# 5853-base-board.net
KiCad netlist of a schematic drawn in EAGLE
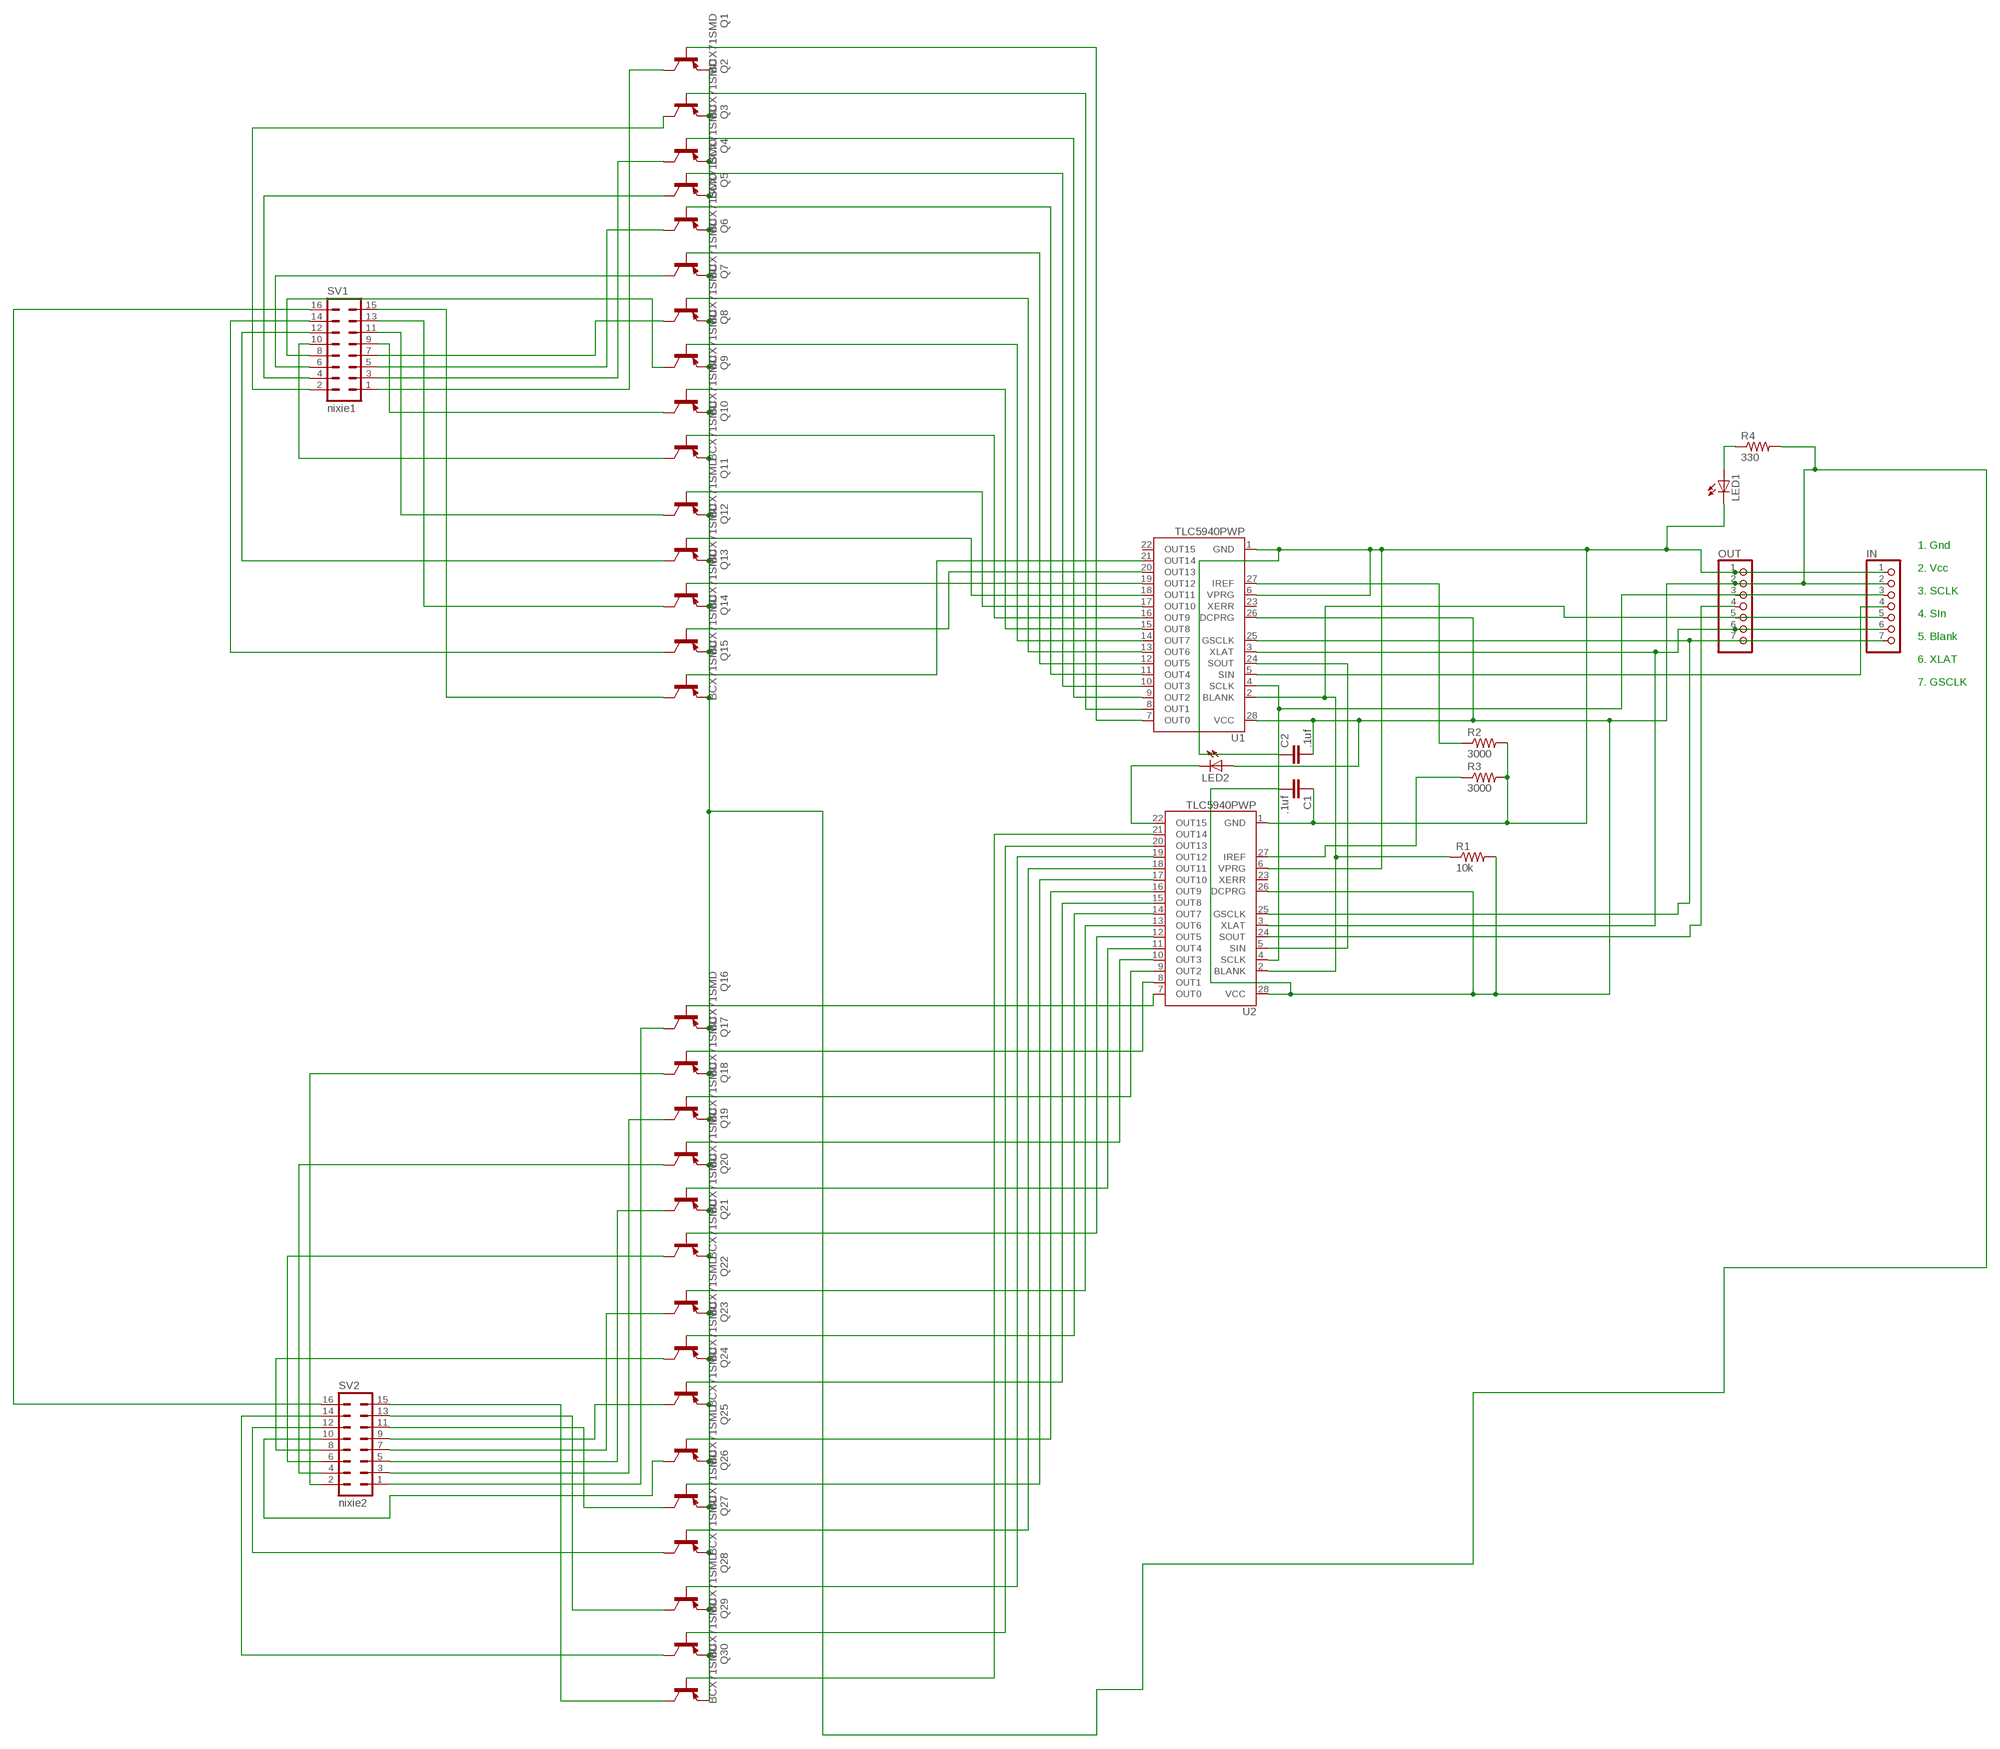
[diagram p0: schematic, sheet 1]

(export (version "E")
  (design (tool "Eeschema 10.0.6"))
  (components
    (comp (ref "C1")
      (value ".1uf")
      (footprint "eagle-import:C0805K")
      (libsource (lib "eagle-import") (part "C-EUC0805K"))
    )
    (comp (ref "C2")
      (value ".1uf")
      (footprint "eagle-import:C0805K")
      (libsource (lib "eagle-import") (part "C-EUC0805K"))
    )
    (comp (ref "IN")
      (value "PINHD-1X7")
      (footprint "eagle-import:1X07")
      (libsource (lib "eagle-import") (part "PINHD-1X7"))
    )
    (comp (ref "LED1")
      (value "LEDCHIPLED_0603")
      (footprint "eagle-import:CHIPLED_0603")
      (libsource (lib "eagle-import") (part "LEDCHIPLED_0603"))
    )
    (comp (ref "LED2")
      (value "LEDCHIPLED_0603")
      (footprint "eagle-import:CHIPLED_0603")
      (libsource (lib "eagle-import") (part "LEDCHIPLED_0603"))
    )
    (comp (ref "OUT")
      (value "PINHD-1X7")
      (footprint "eagle-import:1X07")
      (libsource (lib "eagle-import") (part "PINHD-1X7"))
    )
    (comp (ref "Q1")
      (value "BCX71SMD")
      (footprint "eagle-import:SOT23")
      (libsource (lib "eagle-import") (part "BCX71SMD"))
    )
    (comp (ref "Q2")
      (value "BCX71SMD")
      (footprint "eagle-import:SOT23")
      (libsource (lib "eagle-import") (part "BCX71SMD"))
    )
    (comp (ref "Q3")
      (value "BCX71SMD")
      (footprint "eagle-import:SOT23")
      (libsource (lib "eagle-import") (part "BCX71SMD"))
    )
    (comp (ref "Q4")
      (value "BCX71SMD")
      (footprint "eagle-import:SOT23")
      (libsource (lib "eagle-import") (part "BCX71SMD"))
    )
    (comp (ref "Q5")
      (value "BCX71SMD")
      (footprint "eagle-import:SOT23")
      (libsource (lib "eagle-import") (part "BCX71SMD"))
    )
    (comp (ref "Q6")
      (value "BCX71SMD")
      (footprint "eagle-import:SOT23")
      (libsource (lib "eagle-import") (part "BCX71SMD"))
    )
    (comp (ref "Q7")
      (value "BCX71SMD")
      (footprint "eagle-import:SOT23")
      (libsource (lib "eagle-import") (part "BCX71SMD"))
    )
    (comp (ref "Q8")
      (value "BCX71SMD")
      (footprint "eagle-import:SOT23")
      (libsource (lib "eagle-import") (part "BCX71SMD"))
    )
    (comp (ref "Q9")
      (value "BCX71SMD")
      (footprint "eagle-import:SOT23")
      (libsource (lib "eagle-import") (part "BCX71SMD"))
    )
    (comp (ref "Q10")
      (value "BCX71SMD")
      (footprint "eagle-import:SOT23")
      (libsource (lib "eagle-import") (part "BCX71SMD"))
    )
    (comp (ref "Q11")
      (value "BCX71SMD")
      (footprint "eagle-import:SOT23")
      (libsource (lib "eagle-import") (part "BCX71SMD"))
    )
    (comp (ref "Q12")
      (value "BCX71SMD")
      (footprint "eagle-import:SOT23")
      (libsource (lib "eagle-import") (part "BCX71SMD"))
    )
    (comp (ref "Q13")
      (value "BCX71SMD")
      (footprint "eagle-import:SOT23")
      (libsource (lib "eagle-import") (part "BCX71SMD"))
    )
    (comp (ref "Q14")
      (value "BCX71SMD")
      (footprint "eagle-import:SOT23")
      (libsource (lib "eagle-import") (part "BCX71SMD"))
    )
    (comp (ref "Q15")
      (value "BCX71SMD")
      (footprint "eagle-import:SOT23")
      (libsource (lib "eagle-import") (part "BCX71SMD"))
    )
    (comp (ref "Q16")
      (value "BCX71SMD")
      (footprint "eagle-import:SOT23")
      (libsource (lib "eagle-import") (part "BCX71SMD"))
    )
    (comp (ref "Q17")
      (value "BCX71SMD")
      (footprint "eagle-import:SOT23")
      (libsource (lib "eagle-import") (part "BCX71SMD"))
    )
    (comp (ref "Q18")
      (value "BCX71SMD")
      (footprint "eagle-import:SOT23")
      (libsource (lib "eagle-import") (part "BCX71SMD"))
    )
    (comp (ref "Q19")
      (value "BCX71SMD")
      (footprint "eagle-import:SOT23")
      (libsource (lib "eagle-import") (part "BCX71SMD"))
    )
    (comp (ref "Q20")
      (value "BCX71SMD")
      (footprint "eagle-import:SOT23")
      (libsource (lib "eagle-import") (part "BCX71SMD"))
    )
    (comp (ref "Q21")
      (value "BCX71SMD")
      (footprint "eagle-import:SOT23")
      (libsource (lib "eagle-import") (part "BCX71SMD"))
    )
    (comp (ref "Q22")
      (value "BCX71SMD")
      (footprint "eagle-import:SOT23")
      (libsource (lib "eagle-import") (part "BCX71SMD"))
    )
    (comp (ref "Q23")
      (value "BCX71SMD")
      (footprint "eagle-import:SOT23")
      (libsource (lib "eagle-import") (part "BCX71SMD"))
    )
    (comp (ref "Q24")
      (value "BCX71SMD")
      (footprint "eagle-import:SOT23")
      (libsource (lib "eagle-import") (part "BCX71SMD"))
    )
    (comp (ref "Q25")
      (value "BCX71SMD")
      (footprint "eagle-import:SOT23")
      (libsource (lib "eagle-import") (part "BCX71SMD"))
    )
    (comp (ref "Q26")
      (value "BCX71SMD")
      (footprint "eagle-import:SOT23")
      (libsource (lib "eagle-import") (part "BCX71SMD"))
    )
    (comp (ref "Q27")
      (value "BCX71SMD")
      (footprint "eagle-import:SOT23")
      (libsource (lib "eagle-import") (part "BCX71SMD"))
    )
    (comp (ref "Q28")
      (value "BCX71SMD")
      (footprint "eagle-import:SOT23")
      (libsource (lib "eagle-import") (part "BCX71SMD"))
    )
    (comp (ref "Q29")
      (value "BCX71SMD")
      (footprint "eagle-import:SOT23")
      (libsource (lib "eagle-import") (part "BCX71SMD"))
    )
    (comp (ref "Q30")
      (value "BCX71SMD")
      (footprint "eagle-import:SOT23")
      (libsource (lib "eagle-import") (part "BCX71SMD"))
    )
    (comp (ref "R1")
      (value "10k")
      (footprint "eagle-import:R0603")
      (libsource (lib "eagle-import") (part "R-US_R0603"))
    )
    (comp (ref "R2")
      (value "3000")
      (footprint "eagle-import:R0603")
      (libsource (lib "eagle-import") (part "R-US_R0603"))
    )
    (comp (ref "R3")
      (value "3000")
      (footprint "eagle-import:R0603")
      (libsource (lib "eagle-import") (part "R-US_R0603"))
    )
    (comp (ref "R4")
      (value "330")
      (footprint "eagle-import:R0603")
      (libsource (lib "eagle-import") (part "R-US_R0603"))
    )
    (comp (ref "SV1")
      (value "nixie1")
      (footprint "eagle-import:ML16")
      (libsource (lib "eagle-import") (part "ML16"))
    )
    (comp (ref "SV2")
      (value "nixie2")
      (footprint "eagle-import:ML16")
      (libsource (lib "eagle-import") (part "ML16"))
    )
    (comp (ref "U1")
      (value "TLC5940PWP")
      (footprint "eagle-import:TSSOP28-GROUNDPAD")
      (libsource (lib "eagle-import") (part "TLC5940PWP"))
    )
    (comp (ref "U2")
      (value "TLC5940PWP")
      (footprint "eagle-import:TSSOP28-GROUNDPAD")
      (libsource (lib "eagle-import") (part "TLC5940PWP"))
    )
  )
  (nets
    (net (code "1") (name "Net-(LED1-PadA)") (class "Default")
      (node (ref "LED1") (pin "A") (pinfunction "A_A") (pintype "passive"))
      (node (ref "R4") (pin "1") (pinfunction "1_1") (pintype "passive"))
    )
    (net (code "2") (name "Net-(Q1-B)") (class "Default")
      (node (ref "Q1") (pin "1") (pinfunction "B_1") (pintype "passive"))
      (node (ref "U1") (pin "7") (pinfunction "OUT0_7") (pintype "bidirectional"))
    )
    (net (code "3") (name "Net-(Q1-C)") (class "Default")
      (node (ref "Q1") (pin "3") (pinfunction "C_3") (pintype "passive"))
      (node (ref "SV1") (pin "1") (pinfunction "1_1") (pintype "passive"))
    )
    (net (code "4") (name "Net-(Q1-E)") (class "Default")
      (node (ref "C1") (pin "2") (pinfunction "2_2") (pintype "passive"))
      (node (ref "C2") (pin "2") (pinfunction "2_2") (pintype "passive"))
      (node (ref "IN") (pin "2") (pinfunction "2_2") (pintype "passive"))
      (node (ref "LED2") (pin "A") (pinfunction "A_A") (pintype "passive"))
      (node (ref "OUT") (pin "2") (pinfunction "2_2") (pintype "passive"))
      (node (ref "Q1") (pin "2") (pinfunction "E_2") (pintype "passive"))
      (node (ref "Q10") (pin "2") (pinfunction "E_2") (pintype "passive"))
      (node (ref "Q11") (pin "2") (pinfunction "E_2") (pintype "passive"))
      (node (ref "Q12") (pin "2") (pinfunction "E_2") (pintype "passive"))
      (node (ref "Q13") (pin "2") (pinfunction "E_2") (pintype "passive"))
      (node (ref "Q14") (pin "2") (pinfunction "E_2") (pintype "passive"))
      (node (ref "Q15") (pin "2") (pinfunction "E_2") (pintype "passive"))
      (node (ref "Q16") (pin "2") (pinfunction "E_2") (pintype "passive"))
      (node (ref "Q17") (pin "2") (pinfunction "E_2") (pintype "passive"))
      (node (ref "Q18") (pin "2") (pinfunction "E_2") (pintype "passive"))
      (node (ref "Q19") (pin "2") (pinfunction "E_2") (pintype "passive"))
      (node (ref "Q2") (pin "2") (pinfunction "E_2") (pintype "passive"))
      (node (ref "Q20") (pin "2") (pinfunction "E_2") (pintype "passive"))
      (node (ref "Q21") (pin "2") (pinfunction "E_2") (pintype "passive"))
      (node (ref "Q22") (pin "2") (pinfunction "E_2") (pintype "passive"))
      (node (ref "Q23") (pin "2") (pinfunction "E_2") (pintype "passive"))
      (node (ref "Q24") (pin "2") (pinfunction "E_2") (pintype "passive"))
      (node (ref "Q25") (pin "2") (pinfunction "E_2") (pintype "passive"))
      (node (ref "Q26") (pin "2") (pinfunction "E_2") (pintype "passive"))
      (node (ref "Q27") (pin "2") (pinfunction "E_2") (pintype "passive"))
      (node (ref "Q28") (pin "2") (pinfunction "E_2") (pintype "passive"))
      (node (ref "Q29") (pin "2") (pinfunction "E_2") (pintype "passive"))
      (node (ref "Q3") (pin "2") (pinfunction "E_2") (pintype "passive"))
      (node (ref "Q30") (pin "2") (pinfunction "E_2") (pintype "passive"))
      (node (ref "Q4") (pin "2") (pinfunction "E_2") (pintype "passive"))
      (node (ref "Q5") (pin "2") (pinfunction "E_2") (pintype "passive"))
      (node (ref "Q6") (pin "2") (pinfunction "E_2") (pintype "passive"))
      (node (ref "Q7") (pin "2") (pinfunction "E_2") (pintype "passive"))
      (node (ref "Q8") (pin "2") (pinfunction "E_2") (pintype "passive"))
      (node (ref "Q9") (pin "2") (pinfunction "E_2") (pintype "passive"))
      (node (ref "R1") (pin "2") (pinfunction "2_2") (pintype "passive"))
      (node (ref "R4") (pin "2") (pinfunction "2_2") (pintype "passive"))
      (node (ref "U1") (pin "26") (pinfunction "DCPRG_26") (pintype "bidirectional"))
      (node (ref "U1") (pin "28") (pinfunction "VCC_28") (pintype "bidirectional"))
      (node (ref "U2") (pin "26") (pinfunction "DCPRG_26") (pintype "bidirectional"))
      (node (ref "U2") (pin "28") (pinfunction "VCC_28") (pintype "bidirectional"))
    )
    (net (code "5") (name "Net-(Q2-B)") (class "Default")
      (node (ref "Q2") (pin "1") (pinfunction "B_1") (pintype "passive"))
      (node (ref "U1") (pin "8") (pinfunction "OUT1_8") (pintype "bidirectional"))
    )
    (net (code "6") (name "Net-(Q2-C)") (class "Default")
      (node (ref "Q2") (pin "3") (pinfunction "C_3") (pintype "passive"))
      (node (ref "SV1") (pin "2") (pinfunction "2_2") (pintype "passive"))
    )
    (net (code "7") (name "Net-(Q3-B)") (class "Default")
      (node (ref "Q3") (pin "1") (pinfunction "B_1") (pintype "passive"))
      (node (ref "U1") (pin "9") (pinfunction "OUT2_9") (pintype "bidirectional"))
    )
    (net (code "8") (name "Net-(Q3-C)") (class "Default")
      (node (ref "Q3") (pin "3") (pinfunction "C_3") (pintype "passive"))
      (node (ref "SV1") (pin "3") (pinfunction "3_3") (pintype "passive"))
    )
    (net (code "9") (name "Net-(Q4-B)") (class "Default")
      (node (ref "Q4") (pin "1") (pinfunction "B_1") (pintype "passive"))
      (node (ref "U1") (pin "10") (pinfunction "OUT3_10") (pintype "bidirectional"))
    )
    (net (code "10") (name "Net-(Q4-C)") (class "Default")
      (node (ref "Q4") (pin "3") (pinfunction "C_3") (pintype "passive"))
      (node (ref "SV1") (pin "4") (pinfunction "4_4") (pintype "passive"))
    )
    (net (code "11") (name "Net-(Q5-B)") (class "Default")
      (node (ref "Q5") (pin "1") (pinfunction "B_1") (pintype "passive"))
      (node (ref "U1") (pin "11") (pinfunction "OUT4_11") (pintype "bidirectional"))
    )
    (net (code "12") (name "Net-(Q5-C)") (class "Default")
      (node (ref "Q5") (pin "3") (pinfunction "C_3") (pintype "passive"))
      (node (ref "SV1") (pin "5") (pinfunction "5_5") (pintype "passive"))
    )
    (net (code "13") (name "Net-(Q6-B)") (class "Default")
      (node (ref "Q6") (pin "1") (pinfunction "B_1") (pintype "passive"))
      (node (ref "U1") (pin "12") (pinfunction "OUT5_12") (pintype "bidirectional"))
    )
    (net (code "14") (name "Net-(Q6-C)") (class "Default")
      (node (ref "Q6") (pin "3") (pinfunction "C_3") (pintype "passive"))
      (node (ref "SV1") (pin "6") (pinfunction "6_6") (pintype "passive"))
    )
    (net (code "15") (name "Net-(Q7-B)") (class "Default")
      (node (ref "Q7") (pin "1") (pinfunction "B_1") (pintype "passive"))
      (node (ref "U1") (pin "13") (pinfunction "OUT6_13") (pintype "bidirectional"))
    )
    (net (code "16") (name "Net-(Q7-C)") (class "Default")
      (node (ref "Q7") (pin "3") (pinfunction "C_3") (pintype "passive"))
      (node (ref "SV1") (pin "7") (pinfunction "7_7") (pintype "passive"))
    )
    (net (code "17") (name "Net-(Q8-B)") (class "Default")
      (node (ref "Q8") (pin "1") (pinfunction "B_1") (pintype "passive"))
      (node (ref "U1") (pin "14") (pinfunction "OUT7_14") (pintype "bidirectional"))
    )
    (net (code "18") (name "Net-(Q8-C)") (class "Default")
      (node (ref "Q8") (pin "3") (pinfunction "C_3") (pintype "passive"))
      (node (ref "SV1") (pin "8") (pinfunction "8_8") (pintype "passive"))
    )
    (net (code "19") (name "Net-(Q9-B)") (class "Default")
      (node (ref "Q9") (pin "1") (pinfunction "B_1") (pintype "passive"))
      (node (ref "U1") (pin "15") (pinfunction "OUT8_15") (pintype "bidirectional"))
    )
    (net (code "20") (name "Net-(Q9-C)") (class "Default")
      (node (ref "Q9") (pin "3") (pinfunction "C_3") (pintype "passive"))
      (node (ref "SV1") (pin "9") (pinfunction "9_9") (pintype "passive"))
    )
    (net (code "21") (name "Net-(Q10-B)") (class "Default")
      (node (ref "Q10") (pin "1") (pinfunction "B_1") (pintype "passive"))
      (node (ref "U1") (pin "16") (pinfunction "OUT9_16") (pintype "bidirectional"))
    )
    (net (code "22") (name "Net-(Q10-C)") (class "Default")
      (node (ref "Q10") (pin "3") (pinfunction "C_3") (pintype "passive"))
      (node (ref "SV1") (pin "10") (pinfunction "10_10") (pintype "passive"))
    )
    (net (code "23") (name "Net-(Q11-B)") (class "Default")
      (node (ref "Q11") (pin "1") (pinfunction "B_1") (pintype "passive"))
      (node (ref "U1") (pin "17") (pinfunction "OUT10_17") (pintype "bidirectional"))
    )
    (net (code "24") (name "Net-(Q11-C)") (class "Default")
      (node (ref "Q11") (pin "3") (pinfunction "C_3") (pintype "passive"))
      (node (ref "SV1") (pin "11") (pinfunction "11_11") (pintype "passive"))
    )
    (net (code "25") (name "Net-(Q12-B)") (class "Default")
      (node (ref "Q12") (pin "1") (pinfunction "B_1") (pintype "passive"))
      (node (ref "U1") (pin "18") (pinfunction "OUT11_18") (pintype "bidirectional"))
    )
    (net (code "26") (name "Net-(Q12-C)") (class "Default")
      (node (ref "Q12") (pin "3") (pinfunction "C_3") (pintype "passive"))
      (node (ref "SV1") (pin "12") (pinfunction "12_12") (pintype "passive"))
    )
    (net (code "27") (name "Net-(Q13-B)") (class "Default")
      (node (ref "Q13") (pin "1") (pinfunction "B_1") (pintype "passive"))
      (node (ref "U1") (pin "19") (pinfunction "OUT12_19") (pintype "bidirectional"))
    )
    (net (code "28") (name "Net-(Q13-C)") (class "Default")
      (node (ref "Q13") (pin "3") (pinfunction "C_3") (pintype "passive"))
      (node (ref "SV1") (pin "13") (pinfunction "13_13") (pintype "passive"))
    )
    (net (code "29") (name "Net-(Q14-B)") (class "Default")
      (node (ref "Q14") (pin "1") (pinfunction "B_1") (pintype "passive"))
      (node (ref "U1") (pin "20") (pinfunction "OUT13_20") (pintype "bidirectional"))
    )
    (net (code "30") (name "Net-(Q14-C)") (class "Default")
      (node (ref "Q14") (pin "3") (pinfunction "C_3") (pintype "passive"))
      (node (ref "SV1") (pin "14") (pinfunction "14_14") (pintype "passive"))
    )
    (net (code "31") (name "Net-(Q15-B)") (class "Default")
      (node (ref "Q15") (pin "1") (pinfunction "B_1") (pintype "passive"))
      (node (ref "U1") (pin "21") (pinfunction "OUT14_21") (pintype "bidirectional"))
    )
    (net (code "32") (name "Net-(Q15-C)") (class "Default")
      (node (ref "Q15") (pin "3") (pinfunction "C_3") (pintype "passive"))
      (node (ref "SV1") (pin "15") (pinfunction "15_15") (pintype "passive"))
    )
    (net (code "33") (name "Net-(Q16-B)") (class "Default")
      (node (ref "Q16") (pin "1") (pinfunction "B_1") (pintype "passive"))
      (node (ref "U2") (pin "7") (pinfunction "OUT0_7") (pintype "bidirectional"))
    )
    (net (code "34") (name "Net-(Q16-C)") (class "Default")
      (node (ref "Q16") (pin "3") (pinfunction "C_3") (pintype "passive"))
      (node (ref "SV2") (pin "1") (pinfunction "1_1") (pintype "passive"))
    )
    (net (code "35") (name "Net-(Q17-B)") (class "Default")
      (node (ref "Q17") (pin "1") (pinfunction "B_1") (pintype "passive"))
      (node (ref "U2") (pin "8") (pinfunction "OUT1_8") (pintype "bidirectional"))
    )
    (net (code "36") (name "Net-(Q17-C)") (class "Default")
      (node (ref "Q17") (pin "3") (pinfunction "C_3") (pintype "passive"))
      (node (ref "SV2") (pin "2") (pinfunction "2_2") (pintype "passive"))
    )
    (net (code "37") (name "Net-(Q18-B)") (class "Default")
      (node (ref "Q18") (pin "1") (pinfunction "B_1") (pintype "passive"))
      (node (ref "U2") (pin "9") (pinfunction "OUT2_9") (pintype "bidirectional"))
    )
    (net (code "38") (name "Net-(Q18-C)") (class "Default")
      (node (ref "Q18") (pin "3") (pinfunction "C_3") (pintype "passive"))
      (node (ref "SV2") (pin "3") (pinfunction "3_3") (pintype "passive"))
    )
    (net (code "39") (name "Net-(Q19-B)") (class "Default")
      (node (ref "Q19") (pin "1") (pinfunction "B_1") (pintype "passive"))
      (node (ref "U2") (pin "10") (pinfunction "OUT3_10") (pintype "bidirectional"))
    )
    (net (code "40") (name "Net-(Q19-C)") (class "Default")
      (node (ref "Q19") (pin "3") (pinfunction "C_3") (pintype "passive"))
      (node (ref "SV2") (pin "4") (pinfunction "4_4") (pintype "passive"))
    )
    (net (code "41") (name "Net-(Q20-B)") (class "Default")
      (node (ref "Q20") (pin "1") (pinfunction "B_1") (pintype "passive"))
      (node (ref "U2") (pin "11") (pinfunction "OUT4_11") (pintype "bidirectional"))
    )
    (net (code "42") (name "Net-(Q20-C)") (class "Default")
      (node (ref "Q20") (pin "3") (pinfunction "C_3") (pintype "passive"))
      (node (ref "SV2") (pin "5") (pinfunction "5_5") (pintype "passive"))
    )
    (net (code "43") (name "Net-(Q21-B)") (class "Default")
      (node (ref "Q21") (pin "1") (pinfunction "B_1") (pintype "passive"))
      (node (ref "U2") (pin "12") (pinfunction "OUT5_12") (pintype "bidirectional"))
    )
    (net (code "44") (name "Net-(Q21-C)") (class "Default")
      (node (ref "Q21") (pin "3") (pinfunction "C_3") (pintype "passive"))
      (node (ref "SV2") (pin "6") (pinfunction "6_6") (pintype "passive"))
    )
    (net (code "45") (name "Net-(Q22-B)") (class "Default")
      (node (ref "Q22") (pin "1") (pinfunction "B_1") (pintype "passive"))
      (node (ref "U2") (pin "13") (pinfunction "OUT6_13") (pintype "bidirectional"))
    )
    (net (code "46") (name "Net-(Q22-C)") (class "Default")
      (node (ref "Q22") (pin "3") (pinfunction "C_3") (pintype "passive"))
      (node (ref "SV2") (pin "7") (pinfunction "7_7") (pintype "passive"))
    )
    (net (code "47") (name "Net-(Q23-B)") (class "Default")
      (node (ref "Q23") (pin "1") (pinfunction "B_1") (pintype "passive"))
      (node (ref "U2") (pin "14") (pinfunction "OUT7_14") (pintype "bidirectional"))
    )
    (net (code "48") (name "Net-(Q23-C)") (class "Default")
      (node (ref "Q23") (pin "3") (pinfunction "C_3") (pintype "passive"))
      (node (ref "SV2") (pin "8") (pinfunction "8_8") (pintype "passive"))
    )
    (net (code "49") (name "Net-(Q24-B)") (class "Default")
      (node (ref "Q24") (pin "1") (pinfunction "B_1") (pintype "passive"))
      (node (ref "U2") (pin "15") (pinfunction "OUT8_15") (pintype "bidirectional"))
    )
    (net (code "50") (name "Net-(Q24-C)") (class "Default")
      (node (ref "Q24") (pin "3") (pinfunction "C_3") (pintype "passive"))
      (node (ref "SV2") (pin "9") (pinfunction "9_9") (pintype "passive"))
    )
    (net (code "51") (name "Net-(Q25-B)") (class "Default")
      (node (ref "Q25") (pin "1") (pinfunction "B_1") (pintype "passive"))
      (node (ref "U2") (pin "16") (pinfunction "OUT9_16") (pintype "bidirectional"))
    )
    (net (code "52") (name "Net-(Q25-C)") (class "Default")
      (node (ref "Q25") (pin "3") (pinfunction "C_3") (pintype "passive"))
      (node (ref "SV2") (pin "10") (pinfunction "10_10") (pintype "passive"))
    )
    (net (code "53") (name "Net-(Q26-B)") (class "Default")
      (node (ref "Q26") (pin "1") (pinfunction "B_1") (pintype "passive"))
      (node (ref "U2") (pin "17") (pinfunction "OUT10_17") (pintype "bidirectional"))
    )
    (net (code "54") (name "Net-(Q26-C)") (class "Default")
      (node (ref "Q26") (pin "3") (pinfunction "C_3") (pintype "passive"))
      (node (ref "SV2") (pin "11") (pinfunction "11_11") (pintype "passive"))
    )
    (net (code "55") (name "Net-(Q27-B)") (class "Default")
      (node (ref "Q27") (pin "1") (pinfunction "B_1") (pintype "passive"))
      (node (ref "U2") (pin "18") (pinfunction "OUT11_18") (pintype "bidirectional"))
    )
    (net (code "56") (name "Net-(Q27-C)") (class "Default")
      (node (ref "Q27") (pin "3") (pinfunction "C_3") (pintype "passive"))
      (node (ref "SV2") (pin "12") (pinfunction "12_12") (pintype "passive"))
    )
    (net (code "57") (name "Net-(Q28-B)") (class "Default")
      (node (ref "Q28") (pin "1") (pinfunction "B_1") (pintype "passive"))
      (node (ref "U2") (pin "19") (pinfunction "OUT12_19") (pintype "bidirectional"))
    )
    (net (code "58") (name "Net-(Q28-C)") (class "Default")
      (node (ref "Q28") (pin "3") (pinfunction "C_3") (pintype "passive"))
      (node (ref "SV2") (pin "13") (pinfunction "13_13") (pintype "passive"))
    )
    (net (code "59") (name "Net-(Q29-B)") (class "Default")
      (node (ref "Q29") (pin "1") (pinfunction "B_1") (pintype "passive"))
      (node (ref "U2") (pin "20") (pinfunction "OUT13_20") (pintype "bidirectional"))
    )
    (net (code "60") (name "Net-(Q29-C)") (class "Default")
      (node (ref "Q29") (pin "3") (pinfunction "C_3") (pintype "passive"))
      (node (ref "SV2") (pin "14") (pinfunction "14_14") (pintype "passive"))
    )
    (net (code "61") (name "Net-(Q30-B)") (class "Default")
      (node (ref "Q30") (pin "1") (pinfunction "B_1") (pintype "passive"))
      (node (ref "U2") (pin "21") (pinfunction "OUT14_21") (pintype "bidirectional"))
    )
    (net (code "62") (name "Net-(Q30-C)") (class "Default")
      (node (ref "Q30") (pin "3") (pinfunction "C_3") (pintype "passive"))
      (node (ref "SV2") (pin "15") (pinfunction "15_15") (pintype "passive"))
    )
    (net (code "63") (name "Net-(SV1-Pad16)") (class "Default")
      (node (ref "SV1") (pin "16") (pinfunction "16_16") (pintype "passive"))
      (node (ref "SV2") (pin "16") (pinfunction "16_16") (pintype "passive"))
    )
    (net (code "64") (name "Net-(U1-BLANK)") (class "Default")
      (node (ref "IN") (pin "5") (pinfunction "5_5") (pintype "passive"))
      (node (ref "OUT") (pin "5") (pinfunction "5_5") (pintype "passive"))
      (node (ref "R1") (pin "1") (pinfunction "1_1") (pintype "passive"))
      (node (ref "U1") (pin "2") (pinfunction "BLANK_2") (pintype "bidirectional"))
      (node (ref "U2") (pin "2") (pinfunction "BLANK_2") (pintype "bidirectional"))
    )
    (net (code "65") (name "Net-(U1-GND)") (class "Default")
      (node (ref "C1") (pin "1") (pinfunction "1_1") (pintype "passive"))
      (node (ref "C2") (pin "1") (pinfunction "1_1") (pintype "passive"))
      (node (ref "IN") (pin "1") (pinfunction "1_1") (pintype "passive"))
      (node (ref "LED1") (pin "C") (pinfunction "C_C") (pintype "passive"))
      (node (ref "OUT") (pin "1") (pinfunction "1_1") (pintype "passive"))
      (node (ref "R2") (pin "2") (pinfunction "2_2") (pintype "passive"))
      (node (ref "R3") (pin "2") (pinfunction "2_2") (pintype "passive"))
      (node (ref "U1") (pin "1") (pinfunction "GND_1") (pintype "bidirectional"))
      (node (ref "U1") (pin "6") (pinfunction "VPRG_6") (pintype "bidirectional"))
      (node (ref "U2") (pin "1") (pinfunction "GND_1") (pintype "bidirectional"))
      (node (ref "U2") (pin "6") (pinfunction "VPRG_6") (pintype "bidirectional"))
    )
    (net (code "66") (name "Net-(U1-GSCLK)") (class "Default")
      (node (ref "IN") (pin "7") (pinfunction "7_7") (pintype "passive"))
      (node (ref "OUT") (pin "7") (pinfunction "7_7") (pintype "passive"))
      (node (ref "U1") (pin "25") (pinfunction "GSCLK_25") (pintype "bidirectional"))
      (node (ref "U2") (pin "25") (pinfunction "GSCLK_25") (pintype "bidirectional"))
    )
    (net (code "67") (name "Net-(U1-IREF)") (class "Default")
      (node (ref "R2") (pin "1") (pinfunction "1_1") (pintype "passive"))
      (node (ref "U1") (pin "27") (pinfunction "IREF_27") (pintype "bidirectional"))
    )
    (net (code "68") (name "Net-(U1-SCLK)") (class "Default")
      (node (ref "IN") (pin "3") (pinfunction "3_3") (pintype "passive"))
      (node (ref "OUT") (pin "3") (pinfunction "3_3") (pintype "passive"))
      (node (ref "U1") (pin "4") (pinfunction "SCLK_4") (pintype "bidirectional"))
      (node (ref "U2") (pin "4") (pinfunction "SCLK_4") (pintype "bidirectional"))
    )
    (net (code "69") (name "Net-(U1-SIN)") (class "Default")
      (node (ref "IN") (pin "4") (pinfunction "4_4") (pintype "passive"))
      (node (ref "U1") (pin "5") (pinfunction "SIN_5") (pintype "bidirectional"))
    )
    (net (code "70") (name "Net-(U1-SOUT)") (class "Default")
      (node (ref "U1") (pin "24") (pinfunction "SOUT_24") (pintype "bidirectional"))
      (node (ref "U2") (pin "5") (pinfunction "SIN_5") (pintype "bidirectional"))
    )
    (net (code "71") (name "Net-(U1-XLAT)") (class "Default")
      (node (ref "IN") (pin "6") (pinfunction "6_6") (pintype "passive"))
      (node (ref "OUT") (pin "6") (pinfunction "6_6") (pintype "passive"))
      (node (ref "U1") (pin "3") (pinfunction "XLAT_3") (pintype "bidirectional"))
      (node (ref "U2") (pin "3") (pinfunction "XLAT_3") (pintype "bidirectional"))
    )
    (net (code "72") (name "Net-(U2-IREF)") (class "Default")
      (node (ref "R3") (pin "1") (pinfunction "1_1") (pintype "passive"))
      (node (ref "U2") (pin "27") (pinfunction "IREF_27") (pintype "bidirectional"))
    )
    (net (code "73") (name "Net-(U2-OUT15)") (class "Default")
      (node (ref "LED2") (pin "C") (pinfunction "C_C") (pintype "passive"))
      (node (ref "U2") (pin "22") (pinfunction "OUT15_22") (pintype "bidirectional"))
    )
    (net (code "74") (name "Net-(U2-SOUT)") (class "Default")
      (node (ref "OUT") (pin "4") (pinfunction "4_4") (pintype "passive"))
      (node (ref "U2") (pin "24") (pinfunction "SOUT_24") (pintype "bidirectional"))
    )
    (net (code "75") (name "unconnected-(U1-OUT15-Pad22)") (class "Default")
      (node (ref "U1") (pin "22") (pinfunction "OUT15_22") (pintype "bidirectional"))
    )
    (net (code "76") (name "unconnected-(U1-XERR-Pad23)") (class "Default")
      (node (ref "U1") (pin "23") (pinfunction "XERR_23") (pintype "bidirectional"))
    )
    (net (code "77") (name "unconnected-(U2-XERR-Pad23)") (class "Default")
      (node (ref "U2") (pin "23") (pinfunction "XERR_23") (pintype "bidirectional"))
    )
  )
)
